# projet_pcb_bluepill_f103.net
KiCad netlist of a schematic drawn in Altium Designer
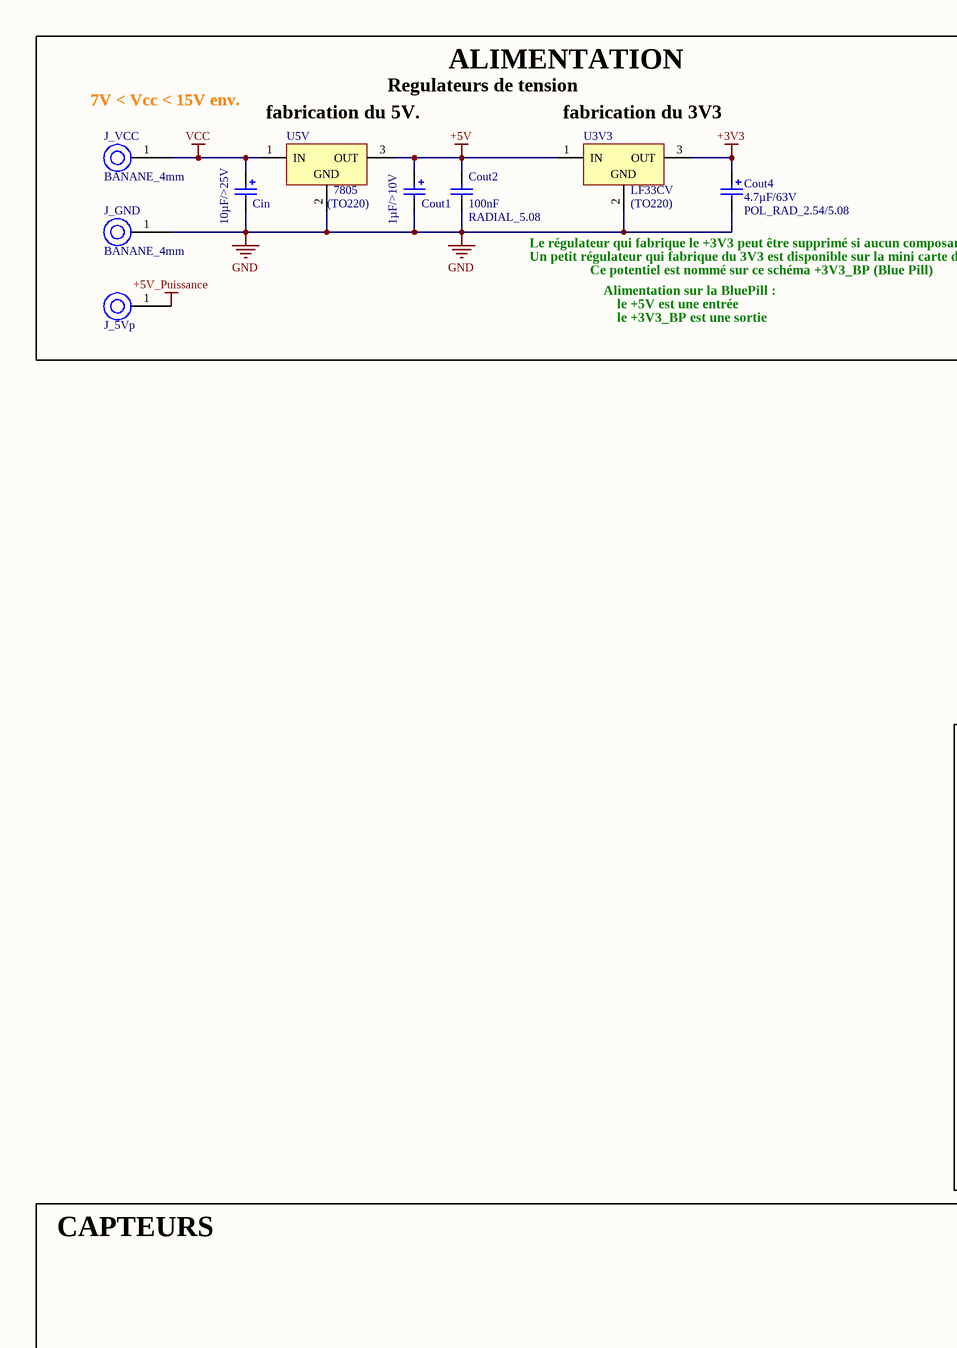
[diagram p0: projet_pcb_bluepill_f103.SchDoc, left]
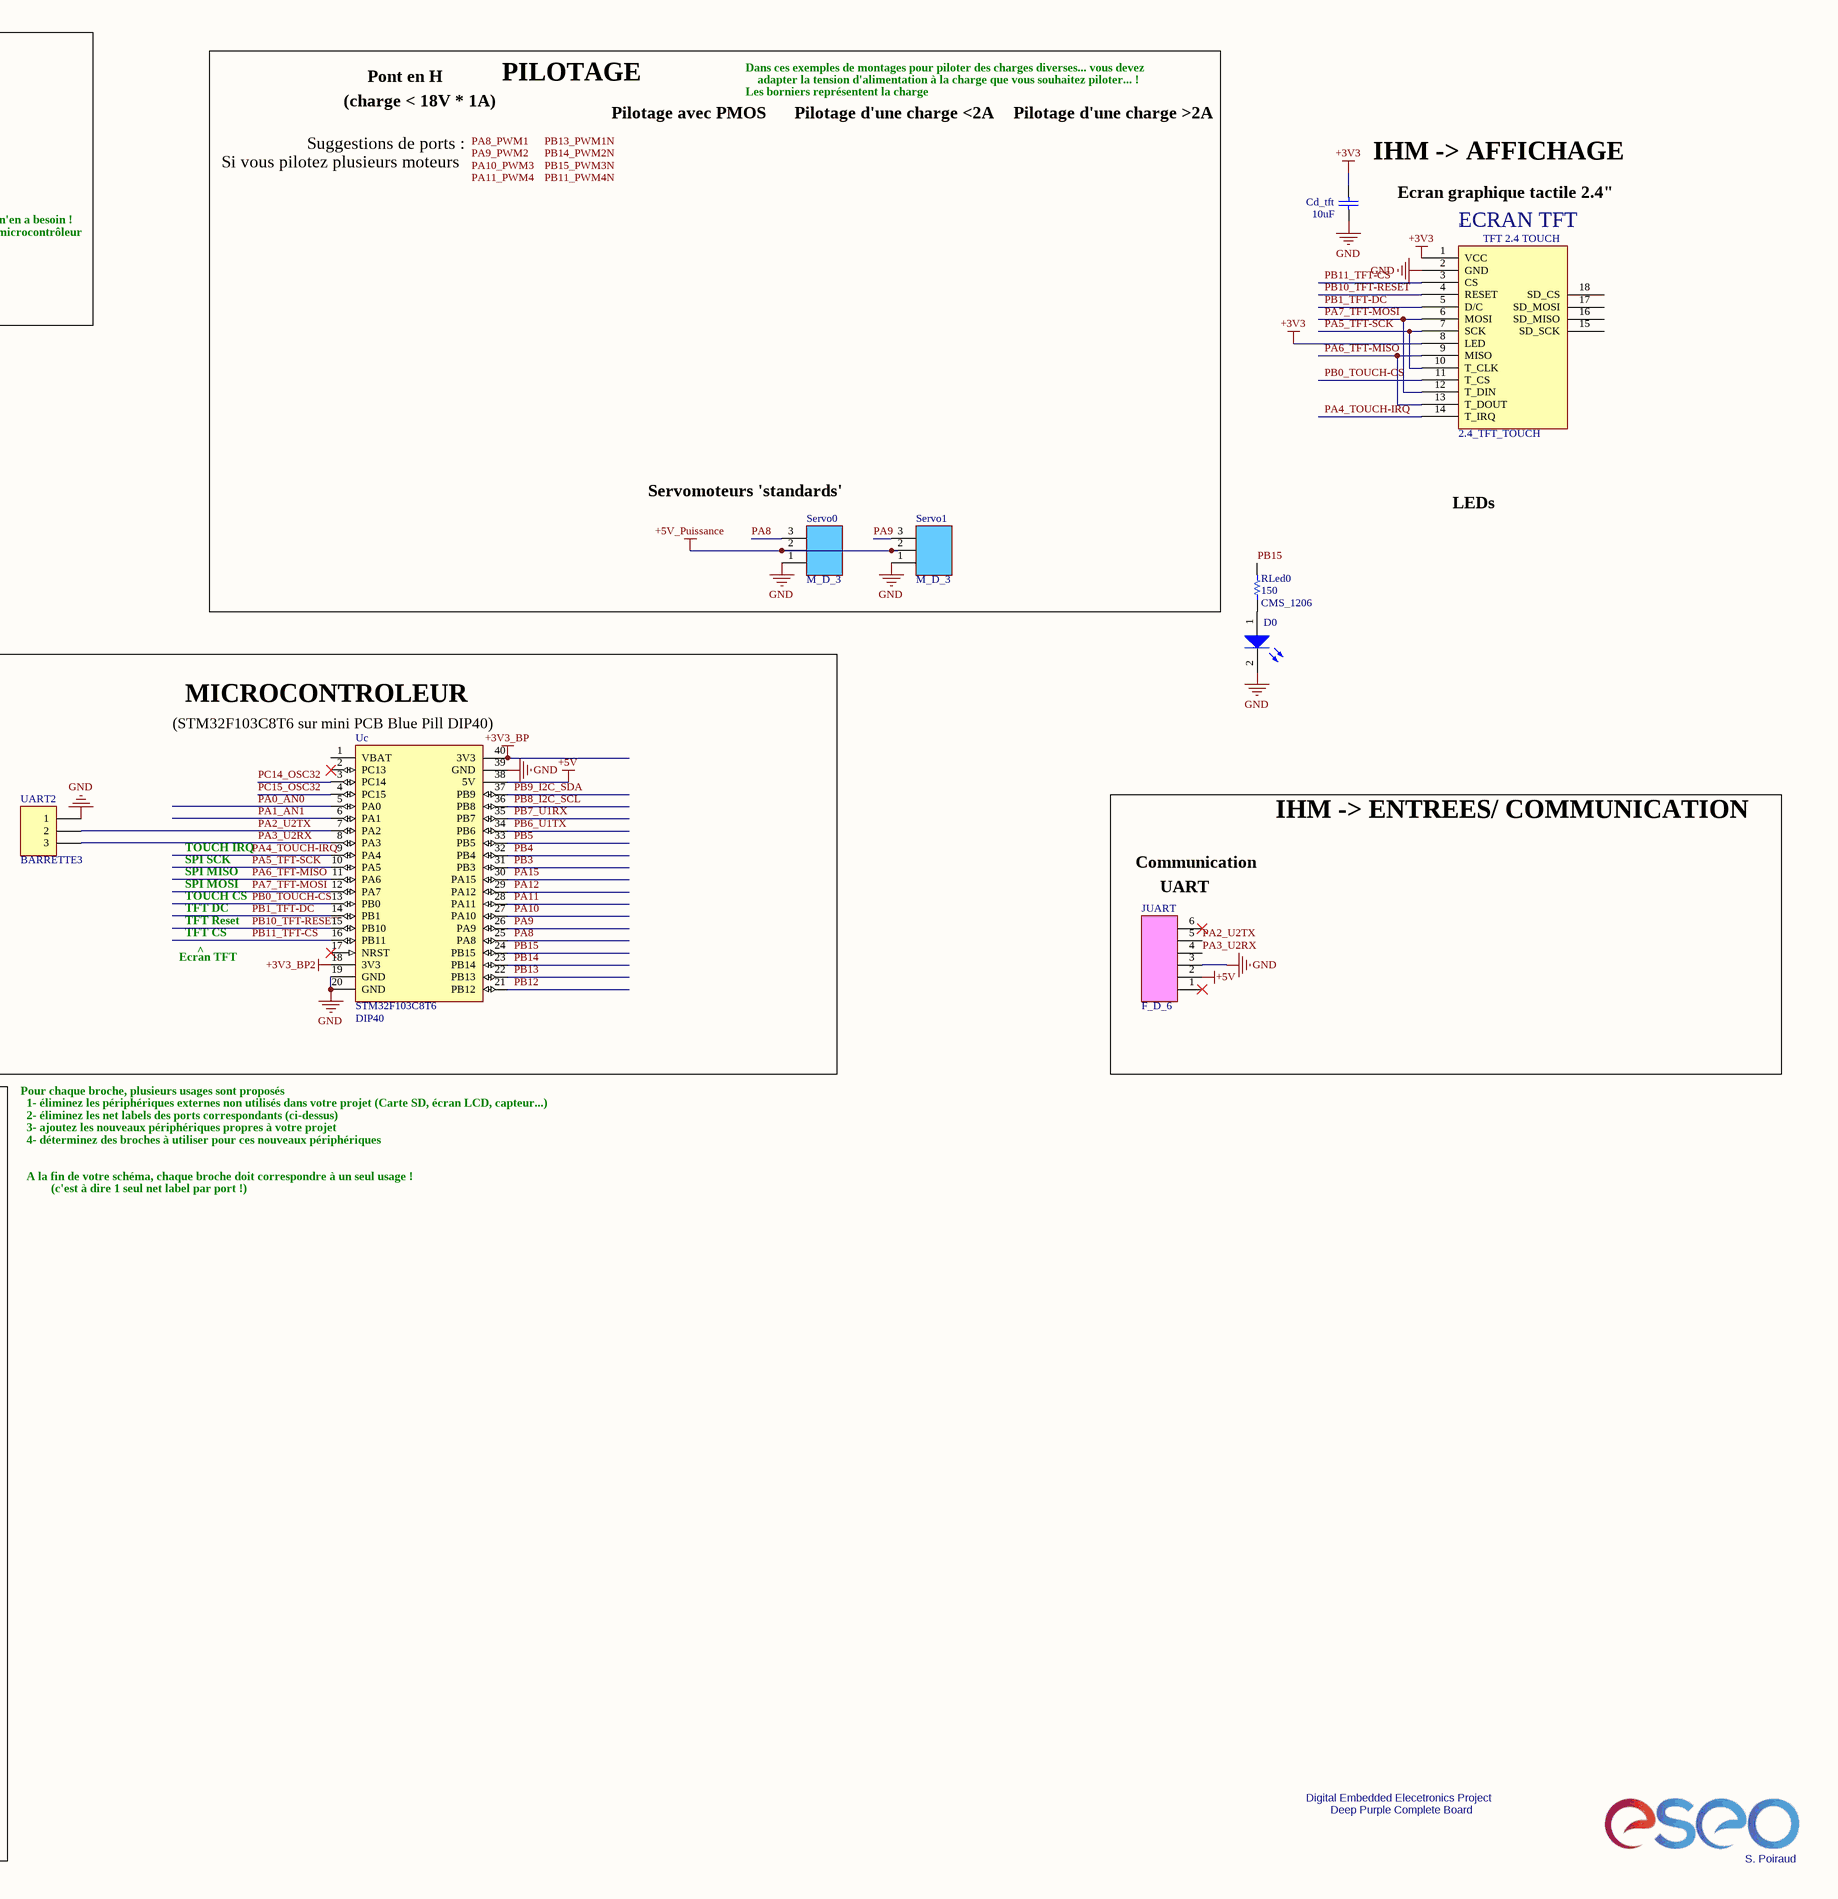
[diagram p1: projet_pcb_bluepill_f103.SchDoc, right]

(export (version "E")
  (design (tool "Eeschema 10.0.6"))
  (components
    (comp (ref "*")
      (value "2.4_TFT_TOUCH")
      (footprint "2.4_TFT_TOUCH")
      (libsource (lib "_ROBOT") (part "2.4_TFT_TOUCH"))
    )
    (comp (ref "Cd_tft")
      (value "10uF")
      (footprint "CONDENSATEUR_POLARISE_ELECTROLYTIQUE_RADIAL_2.54/5.08")
      (description "Capacitor")
      (fields (field (name "PUBLISHER") "Altium Limited"))
      (libsource (lib "_ROBOT") (part "Condensateur"))
    )
    (comp (ref "Cin")
      (value "10µF/>25V")
      (footprint "CONDENSATEUR_POLARISE_ELECTROLYTIQUE_RADIAL_2.0/5.08")
      (description "CONDENSATEUR POLARISE ELECTROLYTIQUE RADIAL 2.0/5.08")
      (fields (field (name "Comment") "CONDENSATEUR_POL_ELECTROLY_RAD_2.0/5.08"))
      (libsource (lib "composants passifs") (part "CONDENSATEUR_POL_ELECTROLY_RAD_2.0/5.08"))
    )
    (comp (ref "Cout1")
      (value "1µF/>10V")
      (footprint "CONDENSATEUR_POLARISE_ELECTROLYTIQUE_RADIAL_2.0/5.08")
      (description "CONDENSATEUR POLARISE ELECTROLYTIQUE RADIAL 2.0/5.08")
      (fields (field (name "Comment") "CONDENSATEUR_POL_ELECTROLY_RAD_2.0/5.08"))
      (libsource (lib "composants passifs") (part "CONDENSATEUR_POL_ELECTROLY_RAD_2.0/5.08"))
    )
    (comp (ref "Cout2")
      (value "100nF")
      (footprint "CONDENSATEUR_CERAMIQUE_RADIAL_5.08")
      (description "CONDENSATEUR TRAVERSANT CERAMIQUE RADIAL 5.08mm")
      (fields (field (name "TYPE") "RADIAL_5.08") (field (name "Comment") "CONDENSATEUR_CER_RAD_5.08"))
      (libsource (lib "composants passifs") (part "CONDENSATEUR_CER_RAD_5.08"))
    )
    (comp (ref "Cout4")
      (value "4.7µF/63V")
      (footprint "CONDENSATEUR_POLARISE_ELECTROLYTIQUE_RADIAL_2.54/5.08")
      (description "CONDENSATEUR POLARISE ELECTROLYTIQUE RADIAL 2.54/5.08")
      (fields
        (field (name "TYPE") "POL_RAD_2.54/5.08")
        (field (name "Comment") "CONDENSATEUR_POL_ELECTROLY_RAD_2.54/5.08")
      )
      (libsource (lib "composants passifs") (part "CONDENSATEUR_POL_ELECTROLY_RAD_2.54/5.08"))
    )
    (comp (ref "D0")
      (value "LED_3MM")
      (footprint "LED_3MM")
      (description "LED 3MM - ROUGE/VERTE/JAUNE")
      (libsource (lib "affichage") (part "LED_3MM"))
    )
    (comp (ref "JUART")
      (value "BARRETTE_6 CONTACTS_1 RANGEE_FEMELLE_DROITE")
      (footprint "BARRETTE_6_F_D")
      (description "BARRETTE 6 CONTACTS 1 RANGEE FEMELLE DROITE")
      (fields (field (name "TYPE") "F_D_6"))
      (libsource (lib "connecteurs") (part "BARRETTE_6 CONTACTS_1 RANGEE_FEMELLE_DROITE"))
    )
    (comp (ref "J_5Vp")
      (value "DOUILLE BANANE 4mm")
      (footprint "DOUILLE_BANANE_4mm")
      (description "DOUILLE BANANE 4 mm")
      (libsource (lib "connecteurs") (part "DOUILLE_BANANE_4mm"))
    )
    (comp (ref "J_GND")
      (value "DOUILLE BANANE 4mm")
      (footprint "DOUILLE_BANANE_4mm")
      (description "DOUILLE BANANE 4 mm")
      (fields (field (name "TYPE") "BANANE_4mm"))
      (libsource (lib "connecteurs") (part "DOUILLE_BANANE_4mm"))
    )
    (comp (ref "J_VCC")
      (value "DOUILLE BANANE 4mm")
      (footprint "DOUILLE_BANANE_4mm")
      (description "DOUILLE BANANE 4 mm")
      (fields (field (name "TYPE") "BANANE_4mm"))
      (libsource (lib "connecteurs") (part "DOUILLE_BANANE_4mm"))
    )
    (comp (ref "RLed0")
      (value "150")
      (footprint "RESISTANCE_CMS_1206")
      (description "RESISTANCE CMS 1206")
      (fields (field (name "TYPE") "CMS_1206") (field (name "Comment") "RESISTANCE_CMS_1206"))
      (libsource (lib "composants passifs") (part "RESISTANCE_CMS_1206"))
    )
    (comp (ref "Servo0")
      (value "BARRETTE 3 CONTACTS 1 RANGEE MALE DROITE")
      (footprint "BARRETTE_3_M_D")
      (fields (field (name "TYPE") "M_D_3"))
      (libsource (lib "connecteurs") (part "BARRETTE_3 CONTACTS_1 RANGEE_MALE_DROITE"))
    )
    (comp (ref "Servo1")
      (value "BARRETTE 3 CONTACTS 1 RANGEE MALE DROITE")
      (footprint "BARRETTE_3_M_D")
      (fields (field (name "TYPE") "M_D_3"))
      (libsource (lib "connecteurs") (part "BARRETTE_3 CONTACTS_1 RANGEE_MALE_DROITE"))
    )
    (comp (ref "U3V3")
      (value "REGULATEUR_TO220_78XX")
      (footprint "REGULATEUR_TO220_78XX")
      (description "REGULATEUR DE TENSION POSITIVE 78XX BOITIER TO220")
      (fields (field (name "TYPE") "LF33CV") (field (name "PACKAGE") "(TO220)"))
      (libsource (lib "composants actifs") (part "REGULATEUR_TO220_78XX"))
    )
    (comp (ref "U5V")
      (value "REGULATEUR_TO220_78XX")
      (footprint "REGULATEUR_TO220_78XX")
      (description "REGULATEUR DE TENSION POSITIVE 78XX BOITIER TO220")
      (fields (field (name "TYPE") "7805") (field (name "PACKAGE") "(TO220)"))
      (libsource (lib "composants actifs") (part "REGULATEUR_TO220_78XX"))
    )
    (comp (ref "UART2")
      (value "BARRETTE3")
      (footprint "HDR1X3")
      (description "Header, 3-Pin")
      (fields (field (name "PUBLISHER") "Altium Limited"))
      (libsource (lib "Connecteur") (part "BARRETTE3"))
    )
    (comp (ref "Uc")
      (value "STM32F103C8T6/PCB_DIP40")
      (footprint "STM32F103C8T6_DIP40")
      (fields (field (name "TYPE") "STM32F103C8T6") (field (name "PACKAGE") "DIP40"))
      (libsource (lib "circuits integres") (part "STM32F103C8T6/PCB_DIP40"))
    )
  )
  (nets
    (net (code "1") (name "+3V3") (class "Default")
      (node (ref "*") (pin "1") (pinfunction "VCC_1") (pintype "passive"))
      (node (ref "*") (pin "8") (pinfunction "LED_8") (pintype "passive"))
      (node (ref "Cd_tft") (pin "1") (pinfunction "1_1") (pintype "passive"))
      (node (ref "Cout4") (pin "1") (pinfunction "1_1") (pintype "passive"))
      (node (ref "U3V3") (pin "3") (pinfunction "OUT_3") (pintype "power_in"))
    )
    (net (code "2") (name "+3V3_BP") (class "Default")
      (node (ref "Uc") (pin "40") (pinfunction "3V3_40") (pintype "power_in"))
    )
    (net (code "3") (name "+3V3_BP2") (class "Default")
      (node (ref "Uc") (pin "18") (pinfunction "3V3_18") (pintype "power_in"))
    )
    (net (code "4") (name "+5V") (class "Default")
      (node (ref "Cout1") (pin "1") (pinfunction "1_1") (pintype "passive"))
      (node (ref "Cout2") (pin "2") (pinfunction "2_2") (pintype "passive"))
      (node (ref "JUART") (pin "2") (pinfunction "2_2") (pintype "passive"))
      (node (ref "U3V3") (pin "1") (pinfunction "IN_1") (pintype "power_in"))
      (node (ref "U5V") (pin "3") (pinfunction "OUT_3") (pintype "power_in"))
      (node (ref "Uc") (pin "38") (pinfunction "5V_38") (pintype "power_in"))
    )
    (net (code "5") (name "+5V_Puissance") (class "Default")
      (node (ref "J_5Vp") (pin "1") (pinfunction "1_1") (pintype "passive"))
      (node (ref "Servo0") (pin "2") (pinfunction "2_2") (pintype "passive"))
      (node (ref "Servo1") (pin "2") (pinfunction "2_2") (pintype "passive"))
    )
    (net (code "6") (name "/PA0_AN0") (class "Default")
      (node (ref "Uc") (pin "5") (pinfunction "PA0_5") (pintype "bidirectional"))
    )
    (net (code "7") (name "/PA1_AN1") (class "Default")
      (node (ref "Uc") (pin "6") (pinfunction "PA1_6") (pintype "bidirectional"))
    )
    (net (code "8") (name "/PA2_U2TX") (class "Default")
      (node (ref "JUART") (pin "5") (pinfunction "5_5") (pintype "passive"))
      (node (ref "UART2") (pin "2") (pinfunction "2_2") (pintype "passive"))
      (node (ref "Uc") (pin "7") (pinfunction "PA2_7") (pintype "bidirectional"))
    )
    (net (code "9") (name "/PA3_U2RX") (class "Default")
      (node (ref "JUART") (pin "4") (pinfunction "4_4") (pintype "passive"))
      (node (ref "UART2") (pin "3") (pinfunction "3_3") (pintype "passive"))
      (node (ref "Uc") (pin "8") (pinfunction "PA3_8") (pintype "bidirectional"))
    )
    (net (code "10") (name "/PA4_TOUCH-IRQ") (class "Default")
      (node (ref "*") (pin "14") (pinfunction "T_IRQ_14") (pintype "passive"))
      (node (ref "Uc") (pin "9") (pinfunction "PA4_9") (pintype "bidirectional"))
    )
    (net (code "11") (name "/PA5_TFT-SCK") (class "Default")
      (node (ref "*") (pin "10") (pinfunction "T_CLK_10") (pintype "passive"))
      (node (ref "*") (pin "7") (pinfunction "SCK_7") (pintype "passive"))
      (node (ref "Uc") (pin "10") (pinfunction "PA5_10") (pintype "bidirectional"))
    )
    (net (code "12") (name "/PA6_TFT-MISO") (class "Default")
      (node (ref "*") (pin "13") (pinfunction "T_DOUT_13") (pintype "passive"))
      (node (ref "*") (pin "9") (pinfunction "MISO_9") (pintype "passive"))
      (node (ref "Uc") (pin "11") (pinfunction "PA6_11") (pintype "bidirectional"))
    )
    (net (code "13") (name "/PA7_TFT-MOSI") (class "Default")
      (node (ref "*") (pin "12") (pinfunction "T_DIN_12") (pintype "passive"))
      (node (ref "*") (pin "6") (pinfunction "MOSI_6") (pintype "passive"))
      (node (ref "Uc") (pin "12") (pinfunction "PA7_12") (pintype "bidirectional"))
    )
    (net (code "14") (name "/PA8") (class "Default")
      (node (ref "Servo0") (pin "3") (pinfunction "3_3") (pintype "passive"))
      (node (ref "Uc") (pin "25") (pinfunction "PA8_25") (pintype "bidirectional"))
    )
    (net (code "16") (name "/PA9") (class "Default")
      (node (ref "Servo1") (pin "3") (pinfunction "3_3") (pintype "passive"))
      (node (ref "Uc") (pin "26") (pinfunction "PA9_26") (pintype "bidirectional"))
    )
    (net (code "18") (name "/PA10") (class "Default")
      (node (ref "Uc") (pin "27") (pinfunction "PA10_27") (pintype "bidirectional"))
    )
    (net (code "20") (name "/PA11") (class "Default")
      (node (ref "Uc") (pin "28") (pinfunction "PA11_28") (pintype "bidirectional"))
    )
    (net (code "22") (name "/PA12") (class "Default")
      (node (ref "Uc") (pin "29") (pinfunction "PA12_29") (pintype "bidirectional"))
    )
    (net (code "23") (name "/PA15") (class "Default")
      (node (ref "Uc") (pin "30") (pinfunction "PA15_30") (pintype "bidirectional"))
    )
    (net (code "24") (name "/PB0_TOUCH-CS") (class "Default")
      (node (ref "*") (pin "11") (pinfunction "T_CS_11") (pintype "passive"))
      (node (ref "Uc") (pin "13") (pinfunction "PB0_13") (pintype "bidirectional"))
    )
    (net (code "25") (name "/PB1_TFT-DC") (class "Default")
      (node (ref "*") (pin "5") (pinfunction "D/C_5") (pintype "passive"))
      (node (ref "Uc") (pin "14") (pinfunction "PB1_14") (pintype "bidirectional"))
    )
    (net (code "26") (name "/PB3") (class "Default")
      (node (ref "Uc") (pin "31") (pinfunction "PB3_31") (pintype "bidirectional"))
    )
    (net (code "27") (name "/PB4") (class "Default")
      (node (ref "Uc") (pin "32") (pinfunction "PB4_32") (pintype "bidirectional"))
    )
    (net (code "28") (name "/PB5") (class "Default")
      (node (ref "Uc") (pin "33") (pinfunction "PB5_33") (pintype "bidirectional"))
    )
    (net (code "29") (name "/PB6_U1TX") (class "Default")
      (node (ref "Uc") (pin "34") (pinfunction "PB6_34") (pintype "bidirectional"))
    )
    (net (code "30") (name "/PB7_U1RX") (class "Default")
      (node (ref "Uc") (pin "35") (pinfunction "PB7_35") (pintype "bidirectional"))
    )
    (net (code "31") (name "/PB8_I2C_SCL") (class "Default")
      (node (ref "Uc") (pin "36") (pinfunction "PB8_36") (pintype "bidirectional"))
    )
    (net (code "32") (name "/PB9_I2C_SDA") (class "Default")
      (node (ref "Uc") (pin "37") (pinfunction "PB9_37") (pintype "bidirectional"))
    )
    (net (code "33") (name "/PB10_TFT-RESET") (class "Default")
      (node (ref "*") (pin "4") (pinfunction "RESET_4") (pintype "passive"))
      (node (ref "Uc") (pin "15") (pinfunction "PB10_15") (pintype "bidirectional"))
    )
    (net (code "35") (name "/PB11_TFT-CS") (class "Default")
      (node (ref "*") (pin "3") (pinfunction "CS_3") (pintype "passive"))
      (node (ref "Uc") (pin "16") (pinfunction "PB11_16") (pintype "bidirectional"))
    )
    (net (code "36") (name "/PB12") (class "Default")
      (node (ref "Uc") (pin "21") (pinfunction "PB12_21") (pintype "bidirectional"))
    )
    (net (code "37") (name "/PB13") (class "Default")
      (node (ref "Uc") (pin "22") (pinfunction "PB13_22") (pintype "bidirectional"))
    )
    (net (code "39") (name "/PB14") (class "Default")
      (node (ref "Uc") (pin "23") (pinfunction "PB14_23") (pintype "bidirectional"))
    )
    (net (code "41") (name "/PB15") (class "Default")
      (node (ref "RLed0") (pin "2") (pinfunction "2_2") (pintype "passive"))
      (node (ref "Uc") (pin "24") (pinfunction "PB15_24") (pintype "bidirectional"))
    )
    (net (code "43") (name "/PC14_OSC32") (class "Default")
      (node (ref "Uc") (pin "3") (pinfunction "PC14_3") (pintype "bidirectional"))
    )
    (net (code "44") (name "/PC15_OSC32") (class "Default")
      (node (ref "Uc") (pin "4") (pinfunction "PC15_4") (pintype "bidirectional"))
    )
    (net (code "45") (name "GND") (class "Default")
      (node (ref "*") (pin "2") (pinfunction "GND_2") (pintype "passive"))
      (node (ref "Cd_tft") (pin "2") (pinfunction "2_2") (pintype "passive"))
      (node (ref "Cin") (pin "2") (pinfunction "2_2") (pintype "passive"))
      (node (ref "Cout1") (pin "2") (pinfunction "2_2") (pintype "passive"))
      (node (ref "Cout2") (pin "1") (pinfunction "1_1") (pintype "passive"))
      (node (ref "Cout4") (pin "2") (pinfunction "2_2") (pintype "passive"))
      (node (ref "D0") (pin "2") (pinfunction "2_2") (pintype "passive"))
      (node (ref "JUART") (pin "3") (pinfunction "3_3") (pintype "passive"))
      (node (ref "J_GND") (pin "1") (pinfunction "1_1") (pintype "passive"))
      (node (ref "Servo0") (pin "1") (pinfunction "1_1") (pintype "passive"))
      (node (ref "Servo1") (pin "1") (pinfunction "1_1") (pintype "passive"))
      (node (ref "U3V3") (pin "2") (pinfunction "GND_2") (pintype "power_in"))
      (node (ref "U5V") (pin "2") (pinfunction "GND_2") (pintype "power_in"))
      (node (ref "UART2") (pin "1") (pinfunction "1_1") (pintype "passive"))
      (node (ref "Uc") (pin "19") (pinfunction "GND_19") (pintype "power_in"))
      (node (ref "Uc") (pin "20") (pinfunction "GND_20") (pintype "power_in"))
      (node (ref "Uc") (pin "39") (pinfunction "GND_39") (pintype "power_in"))
    )
    (net (code "46") (name "Net-(D0-Pad1)") (class "Default")
      (node (ref "D0") (pin "1") (pinfunction "1_1") (pintype "passive"))
      (node (ref "RLed0") (pin "1") (pinfunction "1_1") (pintype "passive"))
    )
    (net (code "47") (name "VCC") (class "Default")
      (node (ref "Cin") (pin "1") (pinfunction "1_1") (pintype "passive"))
      (node (ref "J_VCC") (pin "1") (pinfunction "1_1") (pintype "passive"))
      (node (ref "U5V") (pin "1") (pinfunction "IN_1") (pintype "power_in"))
    )
    (net (code "48") (name "unconnected-(*-SD_CS-Pad18)") (class "Default")
      (node (ref "*") (pin "18") (pinfunction "SD_CS_18") (pintype "passive"))
    )
    (net (code "49") (name "unconnected-(*-SD_MISO-Pad16)") (class "Default")
      (node (ref "*") (pin "16") (pinfunction "SD_MISO_16") (pintype "passive"))
    )
    (net (code "50") (name "unconnected-(*-SD_MOSI-Pad17)") (class "Default")
      (node (ref "*") (pin "17") (pinfunction "SD_MOSI_17") (pintype "passive"))
    )
    (net (code "51") (name "unconnected-(*-SD_SCK-Pad15)") (class "Default")
      (node (ref "*") (pin "15") (pinfunction "SD_SCK_15") (pintype "passive"))
    )
    (net (code "52") (name "unconnected-(JUART-Pad1)") (class "Default")
      (node (ref "JUART") (pin "1") (pinfunction "1_1") (pintype "passive+no_connect"))
    )
    (net (code "53") (name "unconnected-(JUART-Pad6)") (class "Default")
      (node (ref "JUART") (pin "6") (pinfunction "6_6") (pintype "passive+no_connect"))
    )
    (net (code "54") (name "unconnected-(Uc-NRST-Pad17)") (class "Default")
      (node (ref "Uc") (pin "17") (pinfunction "NRST_17") (pintype "input+no_connect"))
    )
    (net (code "55") (name "unconnected-(Uc-PC13-Pad2)") (class "Default")
      (node (ref "Uc") (pin "2") (pinfunction "PC13_2") (pintype "bidirectional+no_connect"))
    )
    (net (code "56") (name "unconnected-(Uc-VBAT-Pad1)") (class "Default")
      (node (ref "Uc") (pin "1") (pinfunction "VBAT_1") (pintype "power_in"))
    )
  )
)
